# keyboard.net
KiCad netlist of a schematic drawn in Altium Designer
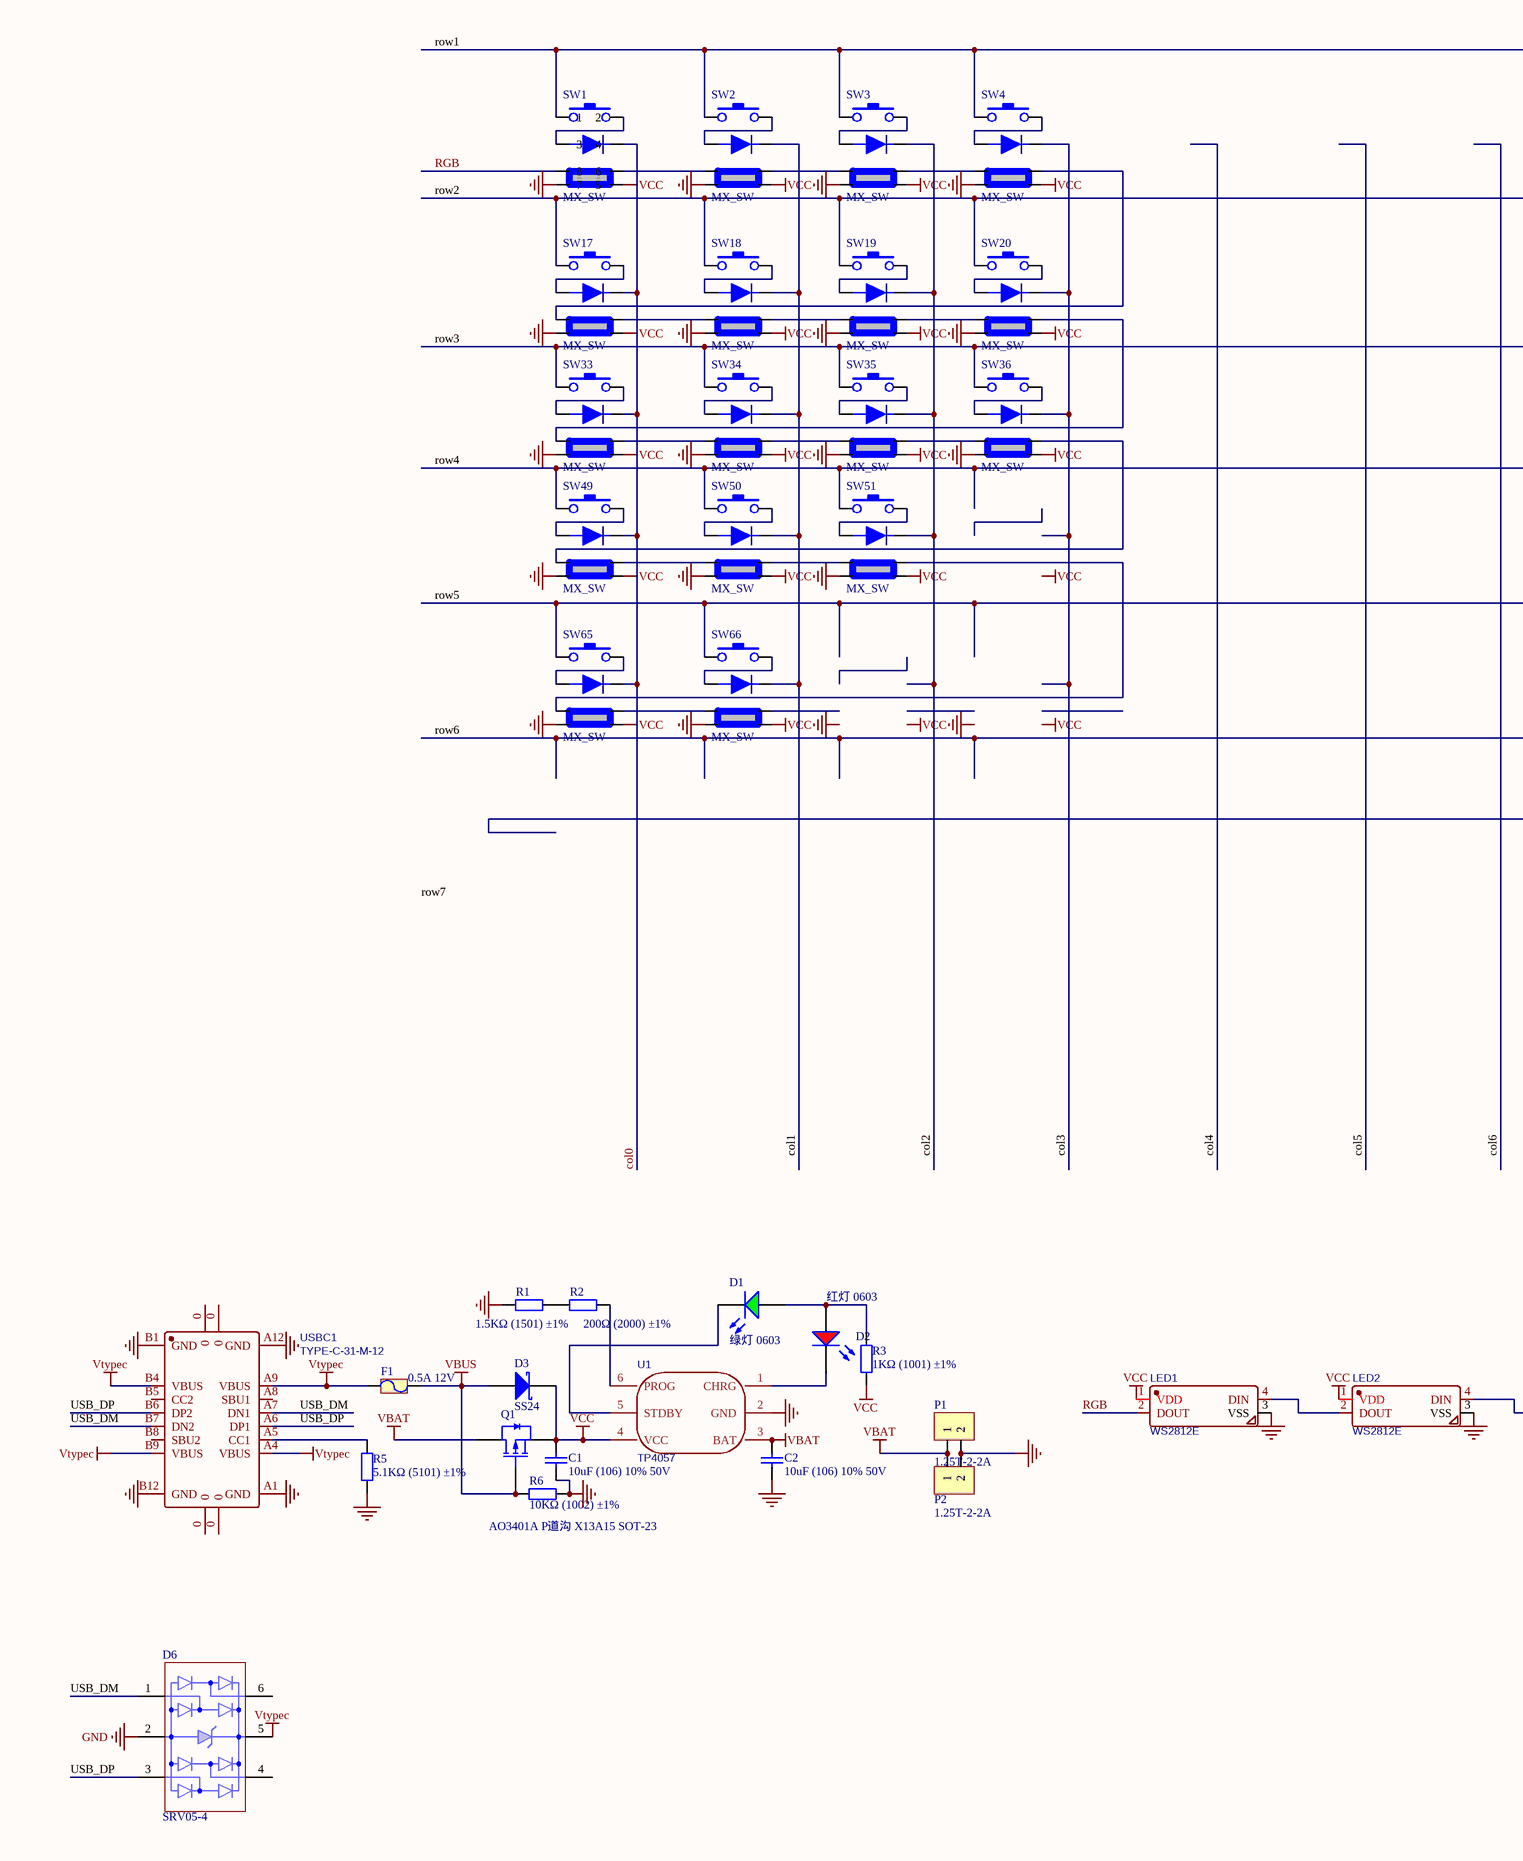
[diagram p0: keyboard.SchDoc, left]
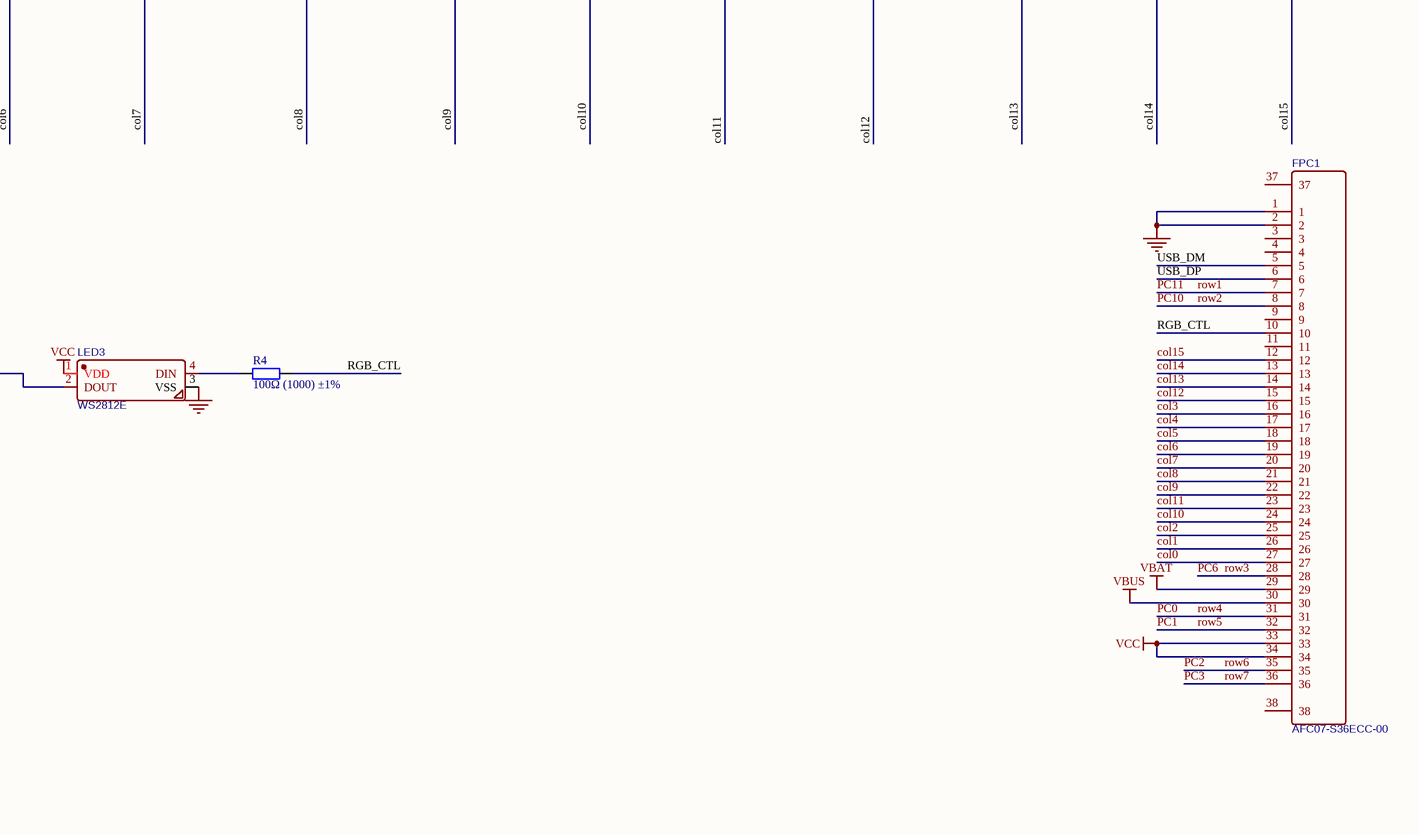
[diagram p1: keyboard.SchDoc, right]

(export (version "E")
  (design (tool "Eeschema 10.0.6"))
  (components
    (comp (ref "C1")
      (value "10uF (106) 10% 50V")
      (footprint "1206_C")
      (description "贴片电容")
      (libsource (lib "Miscellaneous Devices LC") (part "1206 10uF (106) 10% 50V"))
    )
    (comp (ref "C2")
      (value "10uF (106) 10% 50V")
      (footprint "1206_C")
      (description "贴片电容")
      (libsource (lib "Miscellaneous Devices LC") (part "1206 10uF (106) 10% 50V"))
    )
    (comp (ref "D1")
      (value "绿灯 0603")
      (footprint "0603_LED_S1")
      (description "发光二极管")
      (libsource (lib "Miscellaneous Devices LC") (part "0603 绿灯"))
    )
    (comp (ref "D2")
      (value "红灯 0603")
      (footprint "0603_LED_S1")
      (description "发光二极管")
      (libsource (lib "Miscellaneous Devices LC") (part "0603 红灯"))
    )
    (comp (ref "D3")
      (value "SS24")
      (footprint "SMB")
      (description "肖特基二极管")
      (fields
        (field (name "MANUFACTURER") "VISHAY(威世)")
        (field (name "PART NUMBER") "RP02.06.000015")
        (field (name "PUBLISHER") "ChenYinaho")
      )
      (libsource (lib "tsl_Schlib") (part "SS24"))
    )
    (comp (ref "D6")
      (value "SRV05-4")
      (footprint "SOT23-6")
      (description "TVS阵列")
      (fields
        (field (name "MANUFACTURER") "--")
        (field (name "PART NUMBER") "RP02.15.000006")
        (field (name "PUBLISHER") "ChenYinaho")
      )
      (libsource (lib "tsl_Schlib") (part "SRV05-4"))
    )
    (comp (ref "F1")
      (value "0.5A 12V")
      (footprint "R0805")
      (description "自恢复保险")
      (fields (field (name "PART NUMBER") "NEW") (field (name "PUBLISHER") "ChenYinaho"))
      (libsource (lib "tsl_Schlib") (part "Fuse_500mA"))
    )
    (comp (ref "FPC1")
      (value "AFC07-S36ECC-00")
      (footprint "FPC-0.5MM-36P-LCS-SJ-H2.0")
      (fields (field (name "BOM_SUPPLIER PART") "C262254") (field (name "CONTRIBUTOR") "LCSC"))
      (libsource (lib "tsl_Schlib") (part "AFC07-S36ECC-00"))
    )
    (comp (ref "LED1")
      (value "WS2812E")
      (footprint "LED-5050_4P")
      (fields (field (name "BOM_SUPPLIER PART") "C139127") (field (name "CONTRIBUTOR") "LCSC"))
      (libsource (lib "tsl_Schlib") (part "WS2812E"))
    )
    (comp (ref "LED2")
      (value "WS2812E")
      (footprint "LED-5050_4P")
      (fields (field (name "BOM_SUPPLIER PART") "C139127") (field (name "CONTRIBUTOR") "LCSC"))
      (libsource (lib "tsl_Schlib") (part "WS2812E"))
    )
    (comp (ref "LED3")
      (value "WS2812E")
      (footprint "LED-5050_4P")
      (fields (field (name "BOM_SUPPLIER PART") "C139127") (field (name "CONTRIBUTOR") "LCSC"))
      (libsource (lib "tsl_Schlib") (part "WS2812E"))
    )
    (comp (ref "P1")
      (value "1.25T-2-2A")
      (footprint "PH_2PIN_1.25_T_90")
      (description "卧贴座 1.25/2p")
      (fields (field (name "PART NUMBER") "RP02.07.000177") (field (name "PUBLISHER") "ChenYinaho"))
      (libsource (lib "tsl_Schlib") (part "CON2T_90_1"))
    )
    (comp (ref "P2")
      (value "1.25T-2-2A")
      (footprint "PH_2PIN_1.25_T_90")
      (description "卧贴座 1.25/2p")
      (fields (field (name "PART NUMBER") "RP02.07.000177") (field (name "PUBLISHER") "ChenYinaho"))
      (libsource (lib "") (part "CON2T_90_1_1"))
    )
    (comp (ref "Q1")
      (value "AO3401A P道沟 X13A15 SOT-23")
      (footprint "SOT-23-3L")
      (description "MOS(场效应管)")
      (libsource (lib "Miscellaneous Devices LC") (part "AO3401A P道沟 X13A15 SOT-23"))
    )
    (comp (ref "R1")
      (value "1.5KΩ (1501) ±1%")
      (footprint "0603_R")
      (description "贴片电阻")
      (libsource (lib "Miscellaneous Devices LC") (part "0603 1.5KΩ (1501) 1%"))
    )
    (comp (ref "R2")
      (value "200Ω (2000) ±1%")
      (footprint "0603_R")
      (description "贴片电阻")
      (libsource (lib "Miscellaneous Devices LC") (part "0603 200Ω (2000) 1%"))
    )
    (comp (ref "R3")
      (value "1KΩ (1001) ±1%")
      (footprint "0603_R")
      (description "贴片电阻")
      (libsource (lib "Miscellaneous Devices LC") (part "0603 1KΩ (1001) 1%"))
    )
    (comp (ref "R4")
      (value "100Ω (1000) ±1%")
      (footprint "0603_R")
      (description "贴片电阻")
      (libsource (lib "Miscellaneous Devices LC") (part "0603 100Ω (1000) 1%"))
    )
    (comp (ref "R5")
      (value "5.1KΩ (5101) ±1%")
      (footprint "0603_R")
      (description "贴片电阻")
      (libsource (lib "Miscellaneous Devices LC") (part "0603 5.1KΩ (5101) 1%"))
    )
    (comp (ref "R6")
      (value "10KΩ (1002) ±1%")
      (footprint "0603_R")
      (description "贴片电阻")
      (libsource (lib "Miscellaneous Devices LC") (part "0603 10KΩ (1002) 1%"))
    )
    (comp (ref "SW1")
      (value "MX_SW")
      (footprint "MX_SW-7")
      (description "with Fixation pins  1-Pole w/Diode")
      (libsource (lib "") (part "MX_SW-6_1"))
    )
    (comp (ref "SW2")
      (value "MX_SW")
      (footprint "MX_SW-7")
      (description "with Fixation pins  1-Pole w/Diode")
      (libsource (lib "KeyBoard") (part "MX_SW-6"))
    )
    (comp (ref "SW3")
      (value "MX_SW")
      (footprint "MX_SW-7")
      (description "with Fixation pins  1-Pole w/Diode")
      (libsource (lib "KeyBoard") (part "MX_SW-6"))
    )
    (comp (ref "SW4")
      (value "MX_SW")
      (footprint "MX_SW-7")
      (description "with Fixation pins  1-Pole w/Diode")
      (libsource (lib "KeyBoard") (part "MX_SW-6"))
    )
    (comp (ref "SW17")
      (value "MX_SW")
      (footprint "MX_SW-7")
      (description "with Fixation pins  1-Pole w/Diode")
      (libsource (lib "KeyBoard") (part "MX_SW-6"))
    )
    (comp (ref "SW18")
      (value "MX_SW")
      (footprint "MX_SW-7")
      (description "with Fixation pins  1-Pole w/Diode")
      (libsource (lib "KeyBoard") (part "MX_SW-6"))
    )
    (comp (ref "SW19")
      (value "MX_SW")
      (footprint "MX_SW-7")
      (description "with Fixation pins  1-Pole w/Diode")
      (libsource (lib "KeyBoard") (part "MX_SW-6"))
    )
    (comp (ref "SW20")
      (value "MX_SW")
      (footprint "MX_SW-7")
      (description "with Fixation pins  1-Pole w/Diode")
      (libsource (lib "KeyBoard") (part "MX_SW-6"))
    )
    (comp (ref "SW33")
      (value "MX_SW")
      (footprint "MX_SW-7")
      (description "with Fixation pins  1-Pole w/Diode")
      (libsource (lib "KeyBoard") (part "MX_SW-6"))
    )
    (comp (ref "SW34")
      (value "MX_SW")
      (footprint "MX_SW-7")
      (description "with Fixation pins  1-Pole w/Diode")
      (libsource (lib "KeyBoard") (part "MX_SW-6"))
    )
    (comp (ref "SW35")
      (value "MX_SW")
      (footprint "MX_SW-7")
      (description "with Fixation pins  1-Pole w/Diode")
      (libsource (lib "KeyBoard") (part "MX_SW-6"))
    )
    (comp (ref "SW36")
      (value "MX_SW")
      (footprint "MX_SW-7")
      (description "with Fixation pins  1-Pole w/Diode")
      (libsource (lib "KeyBoard") (part "MX_SW-6"))
    )
    (comp (ref "SW49")
      (value "MX_SW")
      (footprint "MX_SW-7")
      (description "with Fixation pins  1-Pole w/Diode")
      (libsource (lib "KeyBoard") (part "MX_SW-6"))
    )
    (comp (ref "SW50")
      (value "MX_SW")
      (footprint "MX_SW-7")
      (description "with Fixation pins  1-Pole w/Diode")
      (libsource (lib "KeyBoard") (part "MX_SW-6"))
    )
    (comp (ref "SW51")
      (value "MX_SW")
      (footprint "MX_SW-7")
      (description "with Fixation pins  1-Pole w/Diode")
      (libsource (lib "KeyBoard") (part "MX_SW-6"))
    )
    (comp (ref "SW65")
      (value "MX_SW")
      (footprint "MX_SW-7")
      (description "with Fixation pins  1-Pole w/Diode")
      (libsource (lib "KeyBoard") (part "MX_SW-6"))
    )
    (comp (ref "SW66")
      (value "MX_SW")
      (footprint "MX_SW-7")
      (description "with Fixation pins  1-Pole w/Diode")
      (libsource (lib "KeyBoard") (part "MX_SW-6"))
    )
    (comp (ref "U1")
      (value "TP4057")
      (footprint "SOT-23-6")
      (fields (field (name "BOM_SUPPLIER PART") "C12044"))
      (libsource (lib "tsl_Schlib") (part "TP4057"))
    )
    (comp (ref "USBC1")
      (value "TYPE-C-31-M-12")
      (footprint "USB-TYPE-C_16PIN-MALE-TYPE-C-31-M-12")
      (fields (field (name "BOM_SUPPLIER PART") "C165948") (field (name "CONTRIBUTOR") "LCSC"))
      (libsource (lib "tsl_Schlib") (part "TYPE-C-31-M-12"))
    )
  )
  (nets
    (net (code "1") (name "/PC0") (class "Default")
      (node (ref "FPC1") (pin "31") (pinfunction "31_31") (pintype "passive"))
      (node (ref "SW49") (pin "1") (pinfunction "1_1") (pintype "passive"))
      (node (ref "SW50") (pin "1") (pinfunction "1_1") (pintype "passive"))
      (node (ref "SW51") (pin "1") (pinfunction "1_1") (pintype "passive"))
    )
    (net (code "2") (name "/PC1") (class "Default")
      (node (ref "FPC1") (pin "32") (pinfunction "32_32") (pintype "passive"))
      (node (ref "SW65") (pin "1") (pinfunction "1_1") (pintype "passive"))
      (node (ref "SW66") (pin "1") (pinfunction "1_1") (pintype "passive"))
    )
    (net (code "3") (name "/PC2") (class "Default")
      (node (ref "FPC1") (pin "35") (pinfunction "35_35") (pintype "passive"))
    )
    (net (code "4") (name "/PC3") (class "Default")
      (node (ref "FPC1") (pin "36") (pinfunction "36_36") (pintype "passive"))
    )
    (net (code "5") (name "/PC6") (class "Default")
      (node (ref "FPC1") (pin "28") (pinfunction "28_28") (pintype "passive"))
      (node (ref "SW33") (pin "1") (pinfunction "1_1") (pintype "passive"))
      (node (ref "SW34") (pin "1") (pinfunction "1_1") (pintype "passive"))
      (node (ref "SW35") (pin "1") (pinfunction "1_1") (pintype "passive"))
      (node (ref "SW36") (pin "1") (pinfunction "1_1") (pintype "passive"))
    )
    (net (code "6") (name "/PC10") (class "Default")
      (node (ref "FPC1") (pin "8") (pinfunction "8_8") (pintype "passive"))
      (node (ref "SW17") (pin "1") (pinfunction "1_1") (pintype "passive"))
      (node (ref "SW18") (pin "1") (pinfunction "1_1") (pintype "passive"))
      (node (ref "SW19") (pin "1") (pinfunction "1_1") (pintype "passive"))
      (node (ref "SW20") (pin "1") (pinfunction "1_1") (pintype "passive"))
    )
    (net (code "7") (name "/PC11") (class "Default")
      (node (ref "FPC1") (pin "7") (pinfunction "7_7") (pintype "passive"))
      (node (ref "SW1") (pin "1") (pinfunction "1_1") (pintype "passive"))
      (node (ref "SW2") (pin "1") (pinfunction "1_1") (pintype "passive"))
      (node (ref "SW3") (pin "1") (pinfunction "1_1") (pintype "passive"))
      (node (ref "SW4") (pin "1") (pinfunction "1_1") (pintype "passive"))
    )
    (net (code "8") (name "/RGB") (class "Default")
      (node (ref "LED1") (pin "2") (pinfunction "DOUT_2") (pintype "passive"))
      (node (ref "SW1") (pin "8") (pinfunction "8_8") (pintype "passive"))
    )
    (net (code "9") (name "/RGB_CTL") (class "Default")
      (node (ref "FPC1") (pin "10") (pinfunction "10_10") (pintype "passive"))
      (node (ref "R4") (pin "2") (pinfunction "2_2") (pintype "passive"))
    )
    (net (code "10") (name "/USB_DM") (class "Default")
      (node (ref "D6") (pin "1") (pinfunction "1_1") (pintype "passive"))
      (node (ref "FPC1") (pin "5") (pinfunction "5_5") (pintype "passive"))
      (node (ref "USBC1") (pin "A7") (pinfunction "DN1_A7") (pintype "passive"))
      (node (ref "USBC1") (pin "B7") (pinfunction "DN2_B7") (pintype "passive"))
    )
    (net (code "11") (name "/USB_DP") (class "Default")
      (node (ref "D6") (pin "3") (pinfunction "3_3") (pintype "passive"))
      (node (ref "FPC1") (pin "6") (pinfunction "6_6") (pintype "passive"))
      (node (ref "USBC1") (pin "A6") (pinfunction "DP1_A6") (pintype "passive"))
      (node (ref "USBC1") (pin "B6") (pinfunction "DP2_B6") (pintype "passive"))
    )
    (net (code "12") (name "/col0") (class "Default")
      (node (ref "FPC1") (pin "27") (pinfunction "27_27") (pintype "passive"))
      (node (ref "SW1") (pin "4") (pinfunction "4_4") (pintype "passive"))
      (node (ref "SW17") (pin "4") (pinfunction "4_4") (pintype "passive"))
      (node (ref "SW33") (pin "4") (pinfunction "4_4") (pintype "passive"))
      (node (ref "SW49") (pin "4") (pinfunction "4_4") (pintype "passive"))
      (node (ref "SW65") (pin "4") (pinfunction "4_4") (pintype "passive"))
    )
    (net (code "13") (name "/col1") (class "Default")
      (node (ref "FPC1") (pin "26") (pinfunction "26_26") (pintype "passive"))
      (node (ref "SW18") (pin "4") (pinfunction "4_4") (pintype "passive"))
      (node (ref "SW2") (pin "4") (pinfunction "4_4") (pintype "passive"))
      (node (ref "SW34") (pin "4") (pinfunction "4_4") (pintype "passive"))
      (node (ref "SW50") (pin "4") (pinfunction "4_4") (pintype "passive"))
      (node (ref "SW66") (pin "4") (pinfunction "4_4") (pintype "passive"))
    )
    (net (code "14") (name "/col2") (class "Default")
      (node (ref "FPC1") (pin "25") (pinfunction "25_25") (pintype "passive"))
      (node (ref "SW19") (pin "4") (pinfunction "4_4") (pintype "passive"))
      (node (ref "SW3") (pin "4") (pinfunction "4_4") (pintype "passive"))
      (node (ref "SW35") (pin "4") (pinfunction "4_4") (pintype "passive"))
      (node (ref "SW51") (pin "4") (pinfunction "4_4") (pintype "passive"))
    )
    (net (code "15") (name "/col3") (class "Default")
      (node (ref "FPC1") (pin "16") (pinfunction "16_16") (pintype "passive"))
      (node (ref "SW20") (pin "4") (pinfunction "4_4") (pintype "passive"))
      (node (ref "SW36") (pin "4") (pinfunction "4_4") (pintype "passive"))
      (node (ref "SW4") (pin "4") (pinfunction "4_4") (pintype "passive"))
    )
    (net (code "16") (name "/col4") (class "Default")
      (node (ref "FPC1") (pin "17") (pinfunction "17_17") (pintype "passive"))
    )
    (net (code "17") (name "/col5") (class "Default")
      (node (ref "FPC1") (pin "18") (pinfunction "18_18") (pintype "passive"))
    )
    (net (code "18") (name "/col6") (class "Default")
      (node (ref "FPC1") (pin "19") (pinfunction "19_19") (pintype "passive"))
    )
    (net (code "19") (name "/col7") (class "Default")
      (node (ref "FPC1") (pin "20") (pinfunction "20_20") (pintype "passive"))
    )
    (net (code "20") (name "/col8") (class "Default")
      (node (ref "FPC1") (pin "21") (pinfunction "21_21") (pintype "passive"))
    )
    (net (code "21") (name "/col9") (class "Default")
      (node (ref "FPC1") (pin "22") (pinfunction "22_22") (pintype "passive"))
    )
    (net (code "22") (name "/col10") (class "Default")
      (node (ref "FPC1") (pin "24") (pinfunction "24_24") (pintype "passive"))
    )
    (net (code "23") (name "/col11") (class "Default")
      (node (ref "FPC1") (pin "23") (pinfunction "23_23") (pintype "passive"))
    )
    (net (code "24") (name "/col12") (class "Default")
      (node (ref "FPC1") (pin "15") (pinfunction "15_15") (pintype "passive"))
    )
    (net (code "25") (name "/col13") (class "Default")
      (node (ref "FPC1") (pin "14") (pinfunction "14_14") (pintype "passive"))
    )
    (net (code "26") (name "/col14") (class "Default")
      (node (ref "FPC1") (pin "13") (pinfunction "13_13") (pintype "passive"))
    )
    (net (code "27") (name "/col15") (class "Default")
      (node (ref "FPC1") (pin "12") (pinfunction "12_12") (pintype "passive"))
    )
    (net (code "28") (name "GND") (class "Default")
      (node (ref "C1") (pin "1") (pinfunction "1_1") (pintype "passive"))
      (node (ref "C2") (pin "1") (pinfunction "1_1") (pintype "passive"))
      (node (ref "D6") (pin "2") (pinfunction "2_2") (pintype "passive"))
      (node (ref "FPC1") (pin "1") (pinfunction "1_1") (pintype "passive"))
      (node (ref "FPC1") (pin "2") (pinfunction "2_2") (pintype "passive"))
      (node (ref "LED1") (pin "3") (pinfunction "VSS_3") (pintype "passive"))
      (node (ref "LED2") (pin "3") (pinfunction "VSS_3") (pintype "passive"))
      (node (ref "LED3") (pin "3") (pinfunction "VSS_3") (pintype "passive"))
      (node (ref "P1") (pin "2") (pinfunction "2_2") (pintype "passive"))
      (node (ref "P2") (pin "2") (pinfunction "2_2") (pintype "passive"))
      (node (ref "R1") (pin "1") (pinfunction "1_1") (pintype "passive"))
      (node (ref "R5") (pin "1") (pinfunction "1_1") (pintype "passive"))
      (node (ref "R6") (pin "1") (pinfunction "1_1") (pintype "passive"))
      (node (ref "SW1") (pin "7") (pinfunction "7_7") (pintype "passive"))
      (node (ref "SW17") (pin "7") (pinfunction "7_7") (pintype "passive"))
      (node (ref "SW18") (pin "7") (pinfunction "7_7") (pintype "passive"))
      (node (ref "SW19") (pin "7") (pinfunction "7_7") (pintype "passive"))
      (node (ref "SW2") (pin "7") (pinfunction "7_7") (pintype "passive"))
      (node (ref "SW20") (pin "7") (pinfunction "7_7") (pintype "passive"))
      (node (ref "SW3") (pin "7") (pinfunction "7_7") (pintype "passive"))
      (node (ref "SW33") (pin "7") (pinfunction "7_7") (pintype "passive"))
      (node (ref "SW34") (pin "7") (pinfunction "7_7") (pintype "passive"))
      (node (ref "SW35") (pin "7") (pinfunction "7_7") (pintype "passive"))
      (node (ref "SW36") (pin "7") (pinfunction "7_7") (pintype "passive"))
      (node (ref "SW4") (pin "7") (pinfunction "7_7") (pintype "passive"))
      (node (ref "SW49") (pin "7") (pinfunction "7_7") (pintype "passive"))
      (node (ref "SW50") (pin "7") (pinfunction "7_7") (pintype "passive"))
      (node (ref "SW51") (pin "7") (pinfunction "7_7") (pintype "passive"))
      (node (ref "SW65") (pin "7") (pinfunction "7_7") (pintype "passive"))
      (node (ref "SW66") (pin "7") (pinfunction "7_7") (pintype "passive"))
      (node (ref "U1") (pin "2") (pinfunction "GND_2") (pintype "passive"))
      (node (ref "USBC1") (pin "A1") (pinfunction "GND_A1") (pintype "passive"))
      (node (ref "USBC1") (pin "A12") (pinfunction "GND_A12") (pintype "passive"))
      (node (ref "USBC1") (pin "B1") (pinfunction "GND_B1") (pintype "passive"))
      (node (ref "USBC1") (pin "B12") (pinfunction "GND_B12") (pintype "passive"))
    )
    (net (code "29") (name "Net-(D1-PadA)") (class "Default")
      (node (ref "D1") (pin "A") (pinfunction "A_A") (pintype "passive"))
      (node (ref "D2") (pin "A") (pinfunction "A_A") (pintype "passive"))
      (node (ref "R3") (pin "2") (pinfunction "2_2") (pintype "passive"))
    )
    (net (code "30") (name "Net-(LED1-DIN)") (class "Default")
      (node (ref "LED1") (pin "4") (pinfunction "DIN_4") (pintype "passive"))
      (node (ref "LED2") (pin "2") (pinfunction "DOUT_2") (pintype "passive"))
    )
    (net (code "31") (name "Net-(LED2-DIN)") (class "Default")
      (node (ref "LED2") (pin "4") (pinfunction "DIN_4") (pintype "passive"))
      (node (ref "LED3") (pin "2") (pinfunction "DOUT_2") (pintype "passive"))
    )
    (net (code "32") (name "Net-(LED3-DIN)") (class "Default")
      (node (ref "LED3") (pin "4") (pinfunction "DIN_4") (pintype "passive"))
      (node (ref "R4") (pin "1") (pinfunction "1_1") (pintype "passive"))
    )
    (net (code "33") (name "Net-(R1-Pad2)") (class "Default")
      (node (ref "R1") (pin "2") (pinfunction "2_2") (pintype "passive"))
      (node (ref "R2") (pin "1") (pinfunction "1_1") (pintype "passive"))
    )
    (net (code "34") (name "Net-(SW1-Pad2)") (class "Default")
      (node (ref "SW1") (pin "2") (pinfunction "2_2") (pintype "passive"))
      (node (ref "SW1") (pin "3") (pinfunction "3_3") (pintype "passive"))
    )
    (net (code "35") (name "Net-(SW1-Pad6)") (class "Default")
      (node (ref "SW1") (pin "6") (pinfunction "6_6") (pintype "passive"))
      (node (ref "SW2") (pin "8") (pinfunction "8_8") (pintype "passive"))
    )
    (net (code "36") (name "Net-(SW2-Pad2)") (class "Default")
      (node (ref "SW2") (pin "2") (pinfunction "2_2") (pintype "passive"))
      (node (ref "SW2") (pin "3") (pinfunction "3_3") (pintype "passive"))
    )
    (net (code "37") (name "Net-(SW2-Pad6)") (class "Default")
      (node (ref "SW2") (pin "6") (pinfunction "6_6") (pintype "passive"))
      (node (ref "SW3") (pin "8") (pinfunction "8_8") (pintype "passive"))
    )
    (net (code "38") (name "Net-(SW3-Pad2)") (class "Default")
      (node (ref "SW3") (pin "2") (pinfunction "2_2") (pintype "passive"))
      (node (ref "SW3") (pin "3") (pinfunction "3_3") (pintype "passive"))
    )
    (net (code "39") (name "Net-(SW3-Pad6)") (class "Default")
      (node (ref "SW3") (pin "6") (pinfunction "6_6") (pintype "passive"))
      (node (ref "SW4") (pin "8") (pinfunction "8_8") (pintype "passive"))
    )
    (net (code "40") (name "Net-(SW4-Pad2)") (class "Default")
      (node (ref "SW4") (pin "2") (pinfunction "2_2") (pintype "passive"))
      (node (ref "SW4") (pin "3") (pinfunction "3_3") (pintype "passive"))
    )
    (net (code "41") (name "Net-(SW17-Pad2)") (class "Default")
      (node (ref "SW17") (pin "2") (pinfunction "2_2") (pintype "passive"))
      (node (ref "SW17") (pin "3") (pinfunction "3_3") (pintype "passive"))
    )
    (net (code "42") (name "Net-(SW17-Pad6)") (class "Default")
      (node (ref "SW17") (pin "6") (pinfunction "6_6") (pintype "passive"))
      (node (ref "SW18") (pin "8") (pinfunction "8_8") (pintype "passive"))
    )
    (net (code "43") (name "Net-(SW17-Pad8)") (class "Default")
      (node (ref "SW17") (pin "8") (pinfunction "8_8") (pintype "passive"))
      (node (ref "SW4") (pin "6") (pinfunction "6_6") (pintype "passive"))
    )
    (net (code "44") (name "Net-(SW18-Pad2)") (class "Default")
      (node (ref "SW18") (pin "2") (pinfunction "2_2") (pintype "passive"))
      (node (ref "SW18") (pin "3") (pinfunction "3_3") (pintype "passive"))
    )
    (net (code "45") (name "Net-(SW18-Pad6)") (class "Default")
      (node (ref "SW18") (pin "6") (pinfunction "6_6") (pintype "passive"))
      (node (ref "SW19") (pin "8") (pinfunction "8_8") (pintype "passive"))
    )
    (net (code "46") (name "Net-(SW19-Pad2)") (class "Default")
      (node (ref "SW19") (pin "2") (pinfunction "2_2") (pintype "passive"))
      (node (ref "SW19") (pin "3") (pinfunction "3_3") (pintype "passive"))
    )
    (net (code "47") (name "Net-(SW19-Pad6)") (class "Default")
      (node (ref "SW19") (pin "6") (pinfunction "6_6") (pintype "passive"))
      (node (ref "SW20") (pin "8") (pinfunction "8_8") (pintype "passive"))
    )
    (net (code "48") (name "Net-(SW20-Pad2)") (class "Default")
      (node (ref "SW20") (pin "2") (pinfunction "2_2") (pintype "passive"))
      (node (ref "SW20") (pin "3") (pinfunction "3_3") (pintype "passive"))
    )
    (net (code "49") (name "Net-(SW20-Pad6)") (class "Default")
      (node (ref "SW20") (pin "6") (pinfunction "6_6") (pintype "passive"))
      (node (ref "SW33") (pin "8") (pinfunction "8_8") (pintype "passive"))
    )
    (net (code "50") (name "Net-(SW33-Pad2)") (class "Default")
      (node (ref "SW33") (pin "2") (pinfunction "2_2") (pintype "passive"))
      (node (ref "SW33") (pin "3") (pinfunction "3_3") (pintype "passive"))
    )
    (net (code "51") (name "Net-(SW33-Pad6)") (class "Default")
      (node (ref "SW33") (pin "6") (pinfunction "6_6") (pintype "passive"))
      (node (ref "SW34") (pin "8") (pinfunction "8_8") (pintype "passive"))
    )
    (net (code "52") (name "Net-(SW34-Pad2)") (class "Default")
      (node (ref "SW34") (pin "2") (pinfunction "2_2") (pintype "passive"))
      (node (ref "SW34") (pin "3") (pinfunction "3_3") (pintype "passive"))
    )
    (net (code "53") (name "Net-(SW34-Pad6)") (class "Default")
      (node (ref "SW34") (pin "6") (pinfunction "6_6") (pintype "passive"))
      (node (ref "SW35") (pin "8") (pinfunction "8_8") (pintype "passive"))
    )
    (net (code "54") (name "Net-(SW35-Pad2)") (class "Default")
      (node (ref "SW35") (pin "2") (pinfunction "2_2") (pintype "passive"))
      (node (ref "SW35") (pin "3") (pinfunction "3_3") (pintype "passive"))
    )
    (net (code "55") (name "Net-(SW35-Pad6)") (class "Default")
      (node (ref "SW35") (pin "6") (pinfunction "6_6") (pintype "passive"))
      (node (ref "SW36") (pin "8") (pinfunction "8_8") (pintype "passive"))
    )
    (net (code "56") (name "Net-(SW36-Pad2)") (class "Default")
      (node (ref "SW36") (pin "2") (pinfunction "2_2") (pintype "passive"))
      (node (ref "SW36") (pin "3") (pinfunction "3_3") (pintype "passive"))
    )
    (net (code "57") (name "Net-(SW36-Pad6)") (class "Default")
      (node (ref "SW36") (pin "6") (pinfunction "6_6") (pintype "passive"))
      (node (ref "SW49") (pin "8") (pinfunction "8_8") (pintype "passive"))
    )
    (net (code "58") (name "Net-(SW49-Pad2)") (class "Default")
      (node (ref "SW49") (pin "2") (pinfunction "2_2") (pintype "passive"))
      (node (ref "SW49") (pin "3") (pinfunction "3_3") (pintype "passive"))
    )
    (net (code "59") (name "Net-(SW49-Pad6)") (class "Default")
      (node (ref "SW49") (pin "6") (pinfunction "6_6") (pintype "passive"))
      (node (ref "SW50") (pin "8") (pinfunction "8_8") (pintype "passive"))
    )
    (net (code "60") (name "Net-(SW50-Pad2)") (class "Default")
      (node (ref "SW50") (pin "2") (pinfunction "2_2") (pintype "passive"))
      (node (ref "SW50") (pin "3") (pinfunction "3_3") (pintype "passive"))
    )
    (net (code "61") (name "Net-(SW50-Pad6)") (class "Default")
      (node (ref "SW50") (pin "6") (pinfunction "6_6") (pintype "passive"))
      (node (ref "SW51") (pin "8") (pinfunction "8_8") (pintype "passive"))
    )
    (net (code "62") (name "Net-(SW51-Pad2)") (class "Default")
      (node (ref "SW51") (pin "2") (pinfunction "2_2") (pintype "passive"))
      (node (ref "SW51") (pin "3") (pinfunction "3_3") (pintype "passive"))
    )
    (net (code "63") (name "Net-(SW51-Pad6)") (class "Default")
      (node (ref "SW51") (pin "6") (pinfunction "6_6") (pintype "passive"))
      (node (ref "SW65") (pin "8") (pinfunction "8_8") (pintype "passive"))
    )
    (net (code "64") (name "Net-(SW65-Pad2)") (class "Default")
      (node (ref "SW65") (pin "2") (pinfunction "2_2") (pintype "passive"))
      (node (ref "SW65") (pin "3") (pinfunction "3_3") (pintype "passive"))
    )
    (net (code "65") (name "Net-(SW65-Pad6)") (class "Default")
      (node (ref "SW65") (pin "6") (pinfunction "6_6") (pintype "passive"))
      (node (ref "SW66") (pin "8") (pinfunction "8_8") (pintype "passive"))
    )
    (net (code "66") (name "Net-(SW66-Pad2)") (class "Default")
      (node (ref "SW66") (pin "2") (pinfunction "2_2") (pintype "passive"))
      (node (ref "SW66") (pin "3") (pinfunction "3_3") (pintype "passive"))
    )
    (net (code "67") (name "Net-(U1-CHRG)") (class "Default")
      (node (ref "D2") (pin "K") (pinfunction "K_K") (pintype "passive"))
      (node (ref "U1") (pin "1") (pinfunction "CHRG_1") (pintype "passive"))
    )
    (net (code "68") (name "Net-(U1-PROG)") (class "Default")
      (node (ref "R2") (pin "2") (pinfunction "2_2") (pintype "passive"))
      (node (ref "U1") (pin "6") (pinfunction "PROG_6") (pintype "passive"))
    )
    (net (code "69") (name "Net-(U1-STDBY)") (class "Default")
      (node (ref "D1") (pin "K") (pinfunction "K_K") (pintype "passive"))
      (node (ref "U1") (pin "5") (pinfunction "STDBY_5") (pintype "passive"))
    )
    (net (code "70") (name "Net-(USBC1-CC1)") (class "Default")
      (node (ref "R5") (pin "2") (pinfunction "2_2") (pintype "passive"))
      (node (ref "USBC1") (pin "A5") (pinfunction "CC1_A5") (pintype "passive"))
    )
    (net (code "71") (name "VBAT") (class "Default")
      (node (ref "C2") (pin "2") (pinfunction "2_2") (pintype "passive"))
      (node (ref "FPC1") (pin "29") (pinfunction "29_29") (pintype "passive"))
      (node (ref "P1") (pin "1") (pinfunction "1_1") (pintype "passive"))
      (node (ref "P2") (pin "1") (pinfunction "1_1") (pintype "passive"))
      (node (ref "Q1") (pin "3") (pinfunction "D_3") (pintype "passive"))
      (node (ref "U1") (pin "3") (pinfunction "BAT_3") (pintype "passive"))
    )
    (net (code "72") (name "VBUS") (class "Default")
      (node (ref "D3") (pin "1") (pinfunction "A_1") (pintype "passive"))
      (node (ref "F1") (pin "1") (pinfunction "1_1") (pintype "passive"))
      (node (ref "FPC1") (pin "30") (pinfunction "30_30") (pintype "passive"))
      (node (ref "Q1") (pin "1") (pinfunction "G_1") (pintype "passive"))
      (node (ref "R6") (pin "2") (pinfunction "2_2") (pintype "passive"))
    )
    (net (code "73") (name "VCC") (class "Default")
      (node (ref "C1") (pin "2") (pinfunction "2_2") (pintype "passive"))
      (node (ref "D3") (pin "2") (pinfunction "K_2") (pintype "passive"))
      (node (ref "FPC1") (pin "33") (pinfunction "33_33") (pintype "passive"))
      (node (ref "FPC1") (pin "34") (pinfunction "34_34") (pintype "passive"))
      (node (ref "LED1") (pin "1") (pinfunction "VDD_1") (pintype "passive"))
      (node (ref "LED2") (pin "1") (pinfunction "VDD_1") (pintype "passive"))
      (node (ref "LED3") (pin "1") (pinfunction "VDD_1") (pintype "passive"))
      (node (ref "Q1") (pin "2") (pinfunction "S_2") (pintype "passive"))
      (node (ref "R3") (pin "1") (pinfunction "1_1") (pintype "passive"))
      (node (ref "SW1") (pin "5") (pinfunction "5_5") (pintype "passive"))
      (node (ref "SW17") (pin "5") (pinfunction "5_5") (pintype "passive"))
      (node (ref "SW18") (pin "5") (pinfunction "5_5") (pintype "passive"))
      (node (ref "SW19") (pin "5") (pinfunction "5_5") (pintype "passive"))
      (node (ref "SW2") (pin "5") (pinfunction "5_5") (pintype "passive"))
      (node (ref "SW20") (pin "5") (pinfunction "5_5") (pintype "passive"))
      (node (ref "SW3") (pin "5") (pinfunction "5_5") (pintype "passive"))
      (node (ref "SW33") (pin "5") (pinfunction "5_5") (pintype "passive"))
      (node (ref "SW34") (pin "5") (pinfunction "5_5") (pintype "passive"))
      (node (ref "SW35") (pin "5") (pinfunction "5_5") (pintype "passive"))
      (node (ref "SW36") (pin "5") (pinfunction "5_5") (pintype "passive"))
      (node (ref "SW4") (pin "5") (pinfunction "5_5") (pintype "passive"))
      (node (ref "SW49") (pin "5") (pinfunction "5_5") (pintype "passive"))
      (node (ref "SW50") (pin "5") (pinfunction "5_5") (pintype "passive"))
      (node (ref "SW51") (pin "5") (pinfunction "5_5") (pintype "passive"))
      (node (ref "SW65") (pin "5") (pinfunction "5_5") (pintype "passive"))
      (node (ref "SW66") (pin "5") (pinfunction "5_5") (pintype "passive"))
      (node (ref "U1") (pin "4") (pinfunction "VCC_4") (pintype "passive"))
    )
    (net (code "74") (name "Vtypec") (class "Default")
      (node (ref "D6") (pin "5") (pinfunction "5_5") (pintype "passive"))
      (node (ref "F1") (pin "2") (pinfunction "2_2") (pintype "passive"))
      (node (ref "USBC1") (pin "A4") (pinfunction "VBUS_A4") (pintype "passive"))
      (node (ref "USBC1") (pin "A9") (pinfunction "VBUS_A9") (pintype "passive"))
      (node (ref "USBC1") (pin "B4") (pinfunction "VBUS_B4") (pintype "passive"))
      (node (ref "USBC1") (pin "B9") (pinfunction "VBUS_B9") (pintype "passive"))
    )
    (net (code "75") (name "unconnected-(D6-Pad4)") (class "Default")
      (node (ref "D6") (pin "4") (pinfunction "4_4") (pintype "passive"))
    )
    (net (code "76") (name "unconnected-(D6-Pad6)") (class "Default")
      (node (ref "D6") (pin "6") (pinfunction "6_6") (pintype "passive"))
    )
    (net (code "77") (name "unconnected-(FPC1-Pad3)") (class "Default")
      (node (ref "FPC1") (pin "3") (pinfunction "3_3") (pintype "passive"))
    )
    (net (code "78") (name "unconnected-(FPC1-Pad4)") (class "Default")
      (node (ref "FPC1") (pin "4") (pinfunction "4_4") (pintype "passive"))
    )
    (net (code "79") (name "unconnected-(FPC1-Pad9)") (class "Default")
      (node (ref "FPC1") (pin "9") (pinfunction "9_9") (pintype "passive"))
    )
    (net (code "80") (name "unconnected-(FPC1-Pad11)") (class "Default")
      (node (ref "FPC1") (pin "11") (pinfunction "11_11") (pintype "passive"))
    )
    (net (code "81") (name "unconnected-(FPC1-Pad37)") (class "Default")
      (node (ref "FPC1") (pin "37") (pinfunction "37_37") (pintype "passive"))
    )
    (net (code "82") (name "unconnected-(FPC1-Pad38)") (class "Default")
      (node (ref "FPC1") (pin "38") (pinfunction "38_38") (pintype "passive"))
    )
    (net (code "83") (name "unconnected-(SW66-Pad6)") (class "Default")
      (node (ref "SW66") (pin "6") (pinfunction "6_6") (pintype "passive"))
    )
    (net (code "84") (name "unconnected-(USBC1-CC2-PadB5)") (class "Default")
      (node (ref "USBC1") (pin "B5") (pinfunction "CC2_B5") (pintype "passive"))
    )
    (net (code "85") (name "unconnected-(USBC1-Pad0)") (class "Default")
      (node (ref "USBC1") (pin "0") (pinfunction "0_0") (pintype "passive"))
    )
    (net (code "86") (name "unconnected-(USBC1-Pad0)_1") (class "Default")
      (node (ref "USBC1") (pin "0") (pinfunction "0_0") (pintype "passive"))
    )
    (net (code "87") (name "unconnected-(USBC1-Pad0)_2") (class "Default")
      (node (ref "USBC1") (pin "0") (pinfunction "0_0") (pintype "passive"))
    )
    (net (code "88") (name "unconnected-(USBC1-Pad0)_3") (class "Default")
      (node (ref "USBC1") (pin "0") (pinfunction "0_0") (pintype "passive"))
    )
    (net (code "89") (name "unconnected-(USBC1-SBU1-PadA8)") (class "Default")
      (node (ref "USBC1") (pin "A8") (pinfunction "SBU1_A8") (pintype "passive"))
    )
    (net (code "90") (name "unconnected-(USBC1-SBU2-PadB8)") (class "Default")
      (node (ref "USBC1") (pin "B8") (pinfunction "SBU2_B8") (pintype "passive"))
    )
  )
)
